# NTC.net
KiCad netlist of a schematic drawn in Altium Designer
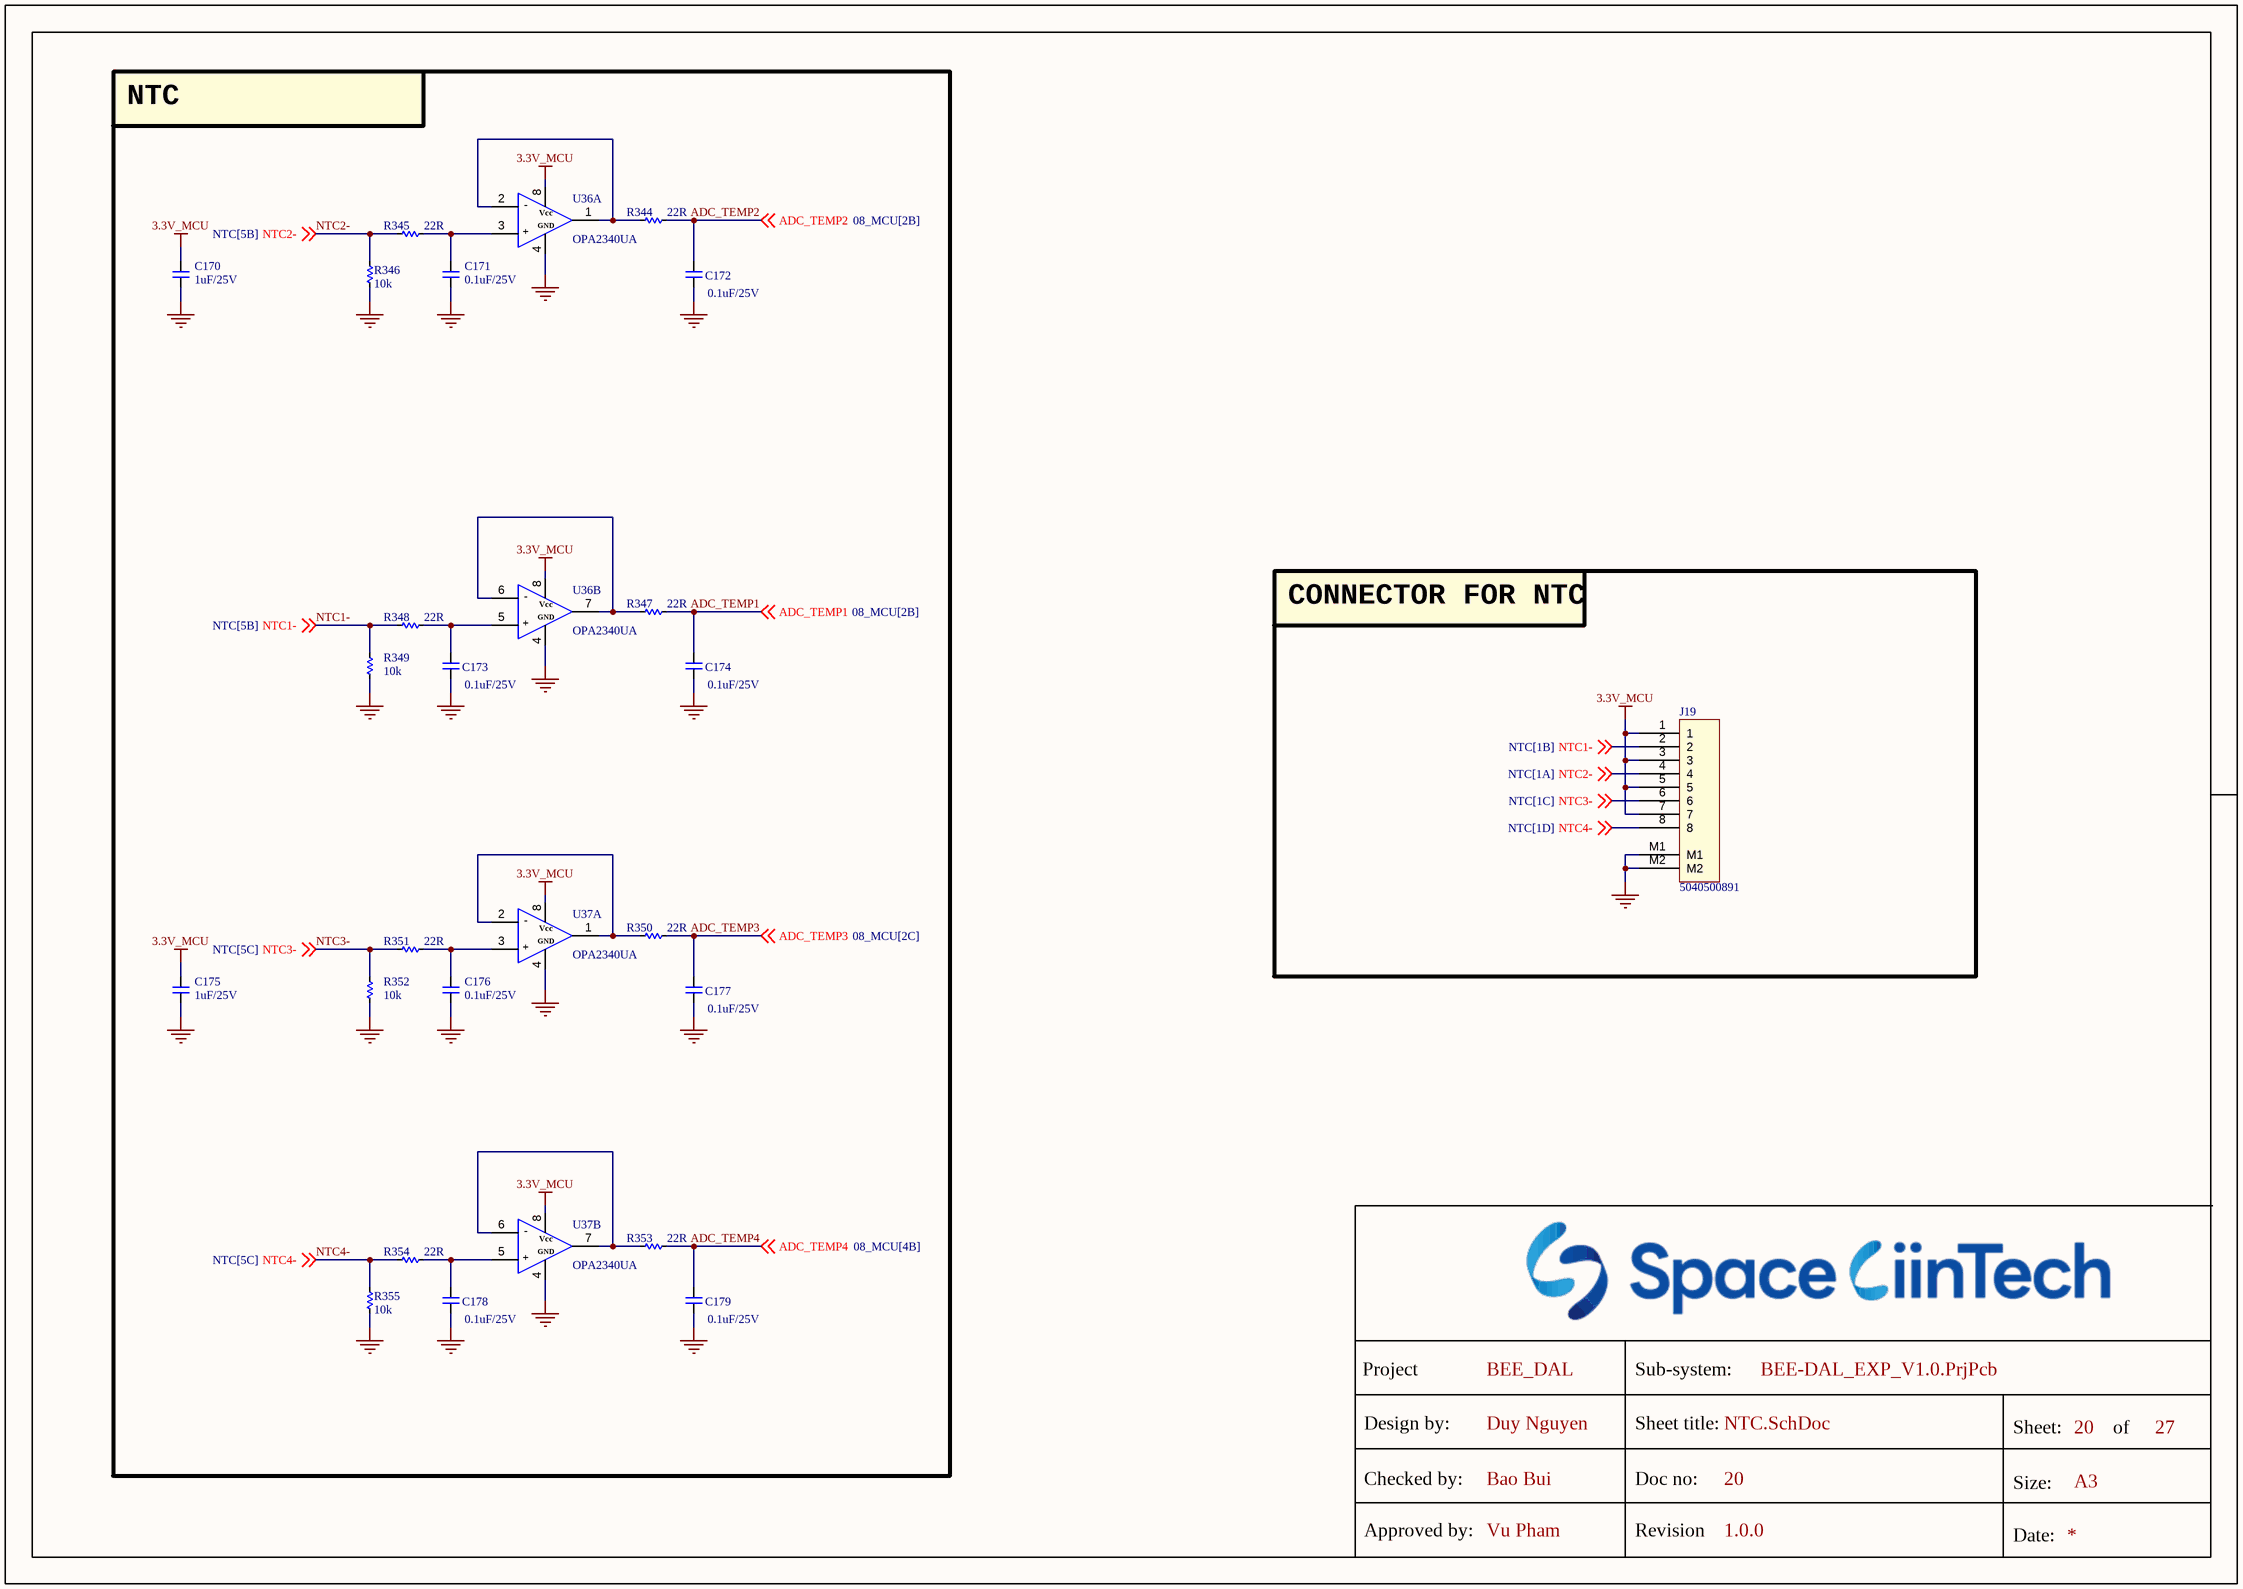
[diagram p0: NTC.SchDoc]

(export (version "E")
  (design (tool "Eeschema 10.0.6"))
  (components
    (comp (ref "C170")
      (value "1uF/25V")
      (footprint "CAP_C_1005X60")
      (description "CAP")
      (libsource (lib "LABLIB") (part "_CAP_C_2"))
    )
    (comp (ref "C171")
      (value "0.1uF/25V")
      (footprint "CAP_C_1005X60")
      (description "CAP")
      (libsource (lib "LABLIB") (part "_CAP_C_2"))
    )
    (comp (ref "C172")
      (value "0.1uF/25V")
      (footprint "CAP_C_1005X60")
      (description "CAP")
      (libsource (lib "LABLIB") (part "_CAP_C_2"))
    )
    (comp (ref "C173")
      (value "0.1uF/25V")
      (footprint "CAP_C_1005X60")
      (description "CAP")
      (libsource (lib "LABLIB") (part "_CAP_C_2"))
    )
    (comp (ref "C174")
      (value "0.1uF/25V")
      (footprint "CAP_C_1005X60")
      (description "CAP")
      (libsource (lib "LABLIB") (part "_CAP_C_2"))
    )
    (comp (ref "C175")
      (value "1uF/25V")
      (footprint "CAP_C_1005X60")
      (description "CAP")
      (libsource (lib "LABLIB") (part "_CAP_C_2"))
    )
    (comp (ref "C176")
      (value "0.1uF/25V")
      (footprint "CAP_C_1005X60")
      (description "CAP")
      (libsource (lib "LABLIB") (part "_CAP_C_2"))
    )
    (comp (ref "C177")
      (value "0.1uF/25V")
      (footprint "CAP_C_1005X60")
      (description "CAP")
      (libsource (lib "LABLIB") (part "_CAP_C_2"))
    )
    (comp (ref "C178")
      (value "0.1uF/25V")
      (footprint "CAP_C_1005X60")
      (description "CAP")
      (libsource (lib "LABLIB") (part "_CAP_C_2"))
    )
    (comp (ref "C179")
      (value "0.1uF/25V")
      (footprint "CAP_C_1005X60")
      (description "CAP")
      (libsource (lib "LABLIB") (part "_CAP_C_2"))
    )
    (comp (ref "J19")
      (value "5040500891")
      (footprint "MOLEX_5040500891")
      (libsource (lib "LABLIB") (part "Header 8x1_2M"))
    )
    (comp (ref "R344")
      (value "22R")
      (footprint "RES_C_1005X40")
      (description "RES")
      (libsource (lib "LABLIB") (part "_RES_B_2"))
    )
    (comp (ref "R345")
      (value "22R")
      (footprint "RES_C_1005X40")
      (description "RES")
      (libsource (lib "LABLIB") (part "_RES_B_2"))
    )
    (comp (ref "R346")
      (value "10k")
      (footprint "RES_C_1005X40")
      (description "RES")
      (libsource (lib "LABLIB") (part "_RES_B_2"))
    )
    (comp (ref "R347")
      (value "22R")
      (footprint "RES_C_1005X40")
      (description "RES")
      (libsource (lib "LABLIB") (part "_RES_B_2"))
    )
    (comp (ref "R348")
      (value "22R")
      (footprint "RES_C_1005X40")
      (description "RES")
      (libsource (lib "LABLIB") (part "_RES_B_2"))
    )
    (comp (ref "R349")
      (value "10k")
      (footprint "RES_C_1005X40")
      (description "RES")
      (libsource (lib "LABLIB") (part "_RES_B_2"))
    )
    (comp (ref "R350")
      (value "22R")
      (footprint "RES_C_1005X40")
      (description "RES")
      (libsource (lib "LABLIB") (part "_RES_B_2"))
    )
    (comp (ref "R351")
      (value "22R")
      (footprint "RES_C_1005X40")
      (description "RES")
      (libsource (lib "LABLIB") (part "_RES_B_2"))
    )
    (comp (ref "R352")
      (value "10k")
      (footprint "RES_C_1005X40")
      (description "RES")
      (libsource (lib "LABLIB") (part "_RES_B_2"))
    )
    (comp (ref "R353")
      (value "22R")
      (footprint "RES_C_1005X40")
      (description "RES")
      (libsource (lib "LABLIB") (part "_RES_B_2"))
    )
    (comp (ref "R354")
      (value "22R")
      (footprint "RES_C_1005X40")
      (description "RES")
      (libsource (lib "LABLIB") (part "_RES_B_2"))
    )
    (comp (ref "R355")
      (value "10k")
      (footprint "RES_C_1005X40")
      (description "RES")
      (libsource (lib "LABLIB") (part "_RES_B_2"))
    )
    (comp (ref "U36")
      (value "OPA2340UA")
      (footprint "SOIC127P602X173-8N")
      (libsource (lib "BEE-DAL_EXP_sche") (part "OPA2340UA"))
    )
    (comp (ref "U37")
      (value "OPA2340UA")
      (footprint "SOIC127P602X173-8N")
      (libsource (lib "BEE-DAL_EXP_sche") (part "OPA2340UA"))
    )
  )
  (nets
    (net (code "1") (name "3.3V_MCU") (class "Default")
      (node (ref "C170") (pin "2") (pinfunction "2_2") (pintype "passive"))
      (node (ref "C175") (pin "2") (pinfunction "2_2") (pintype "passive"))
      (node (ref "J19") (pin "1") (pinfunction "1_1") (pintype "passive"))
      (node (ref "J19") (pin "3") (pinfunction "3_3") (pintype "passive"))
      (node (ref "J19") (pin "5") (pinfunction "5_5") (pintype "passive"))
      (node (ref "J19") (pin "7") (pinfunction "7_7") (pintype "passive"))
      (node (ref "U36") (pin "8") (pinfunction "8_8") (pintype "passive"))
      (node (ref "U37") (pin "8") (pinfunction "8_8") (pintype "passive"))
    )
    (net (code "2") (name "ADC_TEMP1") (class "Default")
      (node (ref "C174") (pin "2") (pinfunction "2_2") (pintype "passive"))
      (node (ref "R347") (pin "2") (pinfunction "2_2") (pintype "passive"))
    )
    (net (code "3") (name "ADC_TEMP2") (class "Default")
      (node (ref "C172") (pin "2") (pinfunction "2_2") (pintype "passive"))
      (node (ref "R344") (pin "2") (pinfunction "2_2") (pintype "passive"))
    )
    (net (code "4") (name "ADC_TEMP3") (class "Default")
      (node (ref "C177") (pin "2") (pinfunction "2_2") (pintype "passive"))
      (node (ref "R350") (pin "2") (pinfunction "2_2") (pintype "passive"))
    )
    (net (code "5") (name "ADC_TEMP4") (class "Default")
      (node (ref "C179") (pin "2") (pinfunction "2_2") (pintype "passive"))
      (node (ref "R353") (pin "2") (pinfunction "2_2") (pintype "passive"))
    )
    (net (code "6") (name "GND") (class "Default")
      (node (ref "C170") (pin "1") (pinfunction "1_1") (pintype "passive"))
      (node (ref "C171") (pin "1") (pinfunction "1_1") (pintype "passive"))
      (node (ref "C172") (pin "1") (pinfunction "1_1") (pintype "passive"))
      (node (ref "C173") (pin "1") (pinfunction "1_1") (pintype "passive"))
      (node (ref "C174") (pin "1") (pinfunction "1_1") (pintype "passive"))
      (node (ref "C175") (pin "1") (pinfunction "1_1") (pintype "passive"))
      (node (ref "C176") (pin "1") (pinfunction "1_1") (pintype "passive"))
      (node (ref "C177") (pin "1") (pinfunction "1_1") (pintype "passive"))
      (node (ref "C178") (pin "1") (pinfunction "1_1") (pintype "passive"))
      (node (ref "C179") (pin "1") (pinfunction "1_1") (pintype "passive"))
      (node (ref "J19") (pin "M1") (pinfunction "M1_M1") (pintype "passive"))
      (node (ref "J19") (pin "M2") (pinfunction "M2_M2") (pintype "passive"))
      (node (ref "R346") (pin "1") (pinfunction "1_1") (pintype "passive"))
      (node (ref "R349") (pin "1") (pinfunction "1_1") (pintype "passive"))
      (node (ref "R352") (pin "1") (pinfunction "1_1") (pintype "passive"))
      (node (ref "R355") (pin "1") (pinfunction "1_1") (pintype "passive"))
      (node (ref "U36") (pin "4") (pinfunction "4_4") (pintype "passive"))
      (node (ref "U37") (pin "4") (pinfunction "4_4") (pintype "passive"))
    )
    (net (code "7") (name "NTC1-") (class "Default")
      (node (ref "J19") (pin "2") (pinfunction "2_2") (pintype "passive"))
      (node (ref "R348") (pin "1") (pinfunction "1_1") (pintype "passive"))
      (node (ref "R349") (pin "2") (pinfunction "2_2") (pintype "passive"))
    )
    (net (code "8") (name "NTC2-") (class "Default")
      (node (ref "J19") (pin "4") (pinfunction "4_4") (pintype "passive"))
      (node (ref "R345") (pin "1") (pinfunction "1_1") (pintype "passive"))
      (node (ref "R346") (pin "2") (pinfunction "2_2") (pintype "passive"))
    )
    (net (code "9") (name "NTC3-") (class "Default")
      (node (ref "J19") (pin "6") (pinfunction "6_6") (pintype "passive"))
      (node (ref "R351") (pin "1") (pinfunction "1_1") (pintype "passive"))
      (node (ref "R352") (pin "2") (pinfunction "2_2") (pintype "passive"))
    )
    (net (code "10") (name "NTC4-") (class "Default")
      (node (ref "J19") (pin "8") (pinfunction "8_8") (pintype "passive"))
      (node (ref "R354") (pin "1") (pinfunction "1_1") (pintype "passive"))
      (node (ref "R355") (pin "2") (pinfunction "2_2") (pintype "passive"))
    )
    (net (code "11") (name "Net-(C171-Pad2)") (class "Default")
      (node (ref "C171") (pin "2") (pinfunction "2_2") (pintype "passive"))
      (node (ref "R345") (pin "2") (pinfunction "2_2") (pintype "passive"))
      (node (ref "U36") (pin "3") (pinfunction "3_3") (pintype "passive"))
    )
    (net (code "12") (name "Net-(C173-Pad2)") (class "Default")
      (node (ref "C173") (pin "2") (pinfunction "2_2") (pintype "passive"))
      (node (ref "R348") (pin "2") (pinfunction "2_2") (pintype "passive"))
      (node (ref "U36") (pin "5") (pinfunction "5_5") (pintype "passive"))
    )
    (net (code "13") (name "Net-(C176-Pad2)") (class "Default")
      (node (ref "C176") (pin "2") (pinfunction "2_2") (pintype "passive"))
      (node (ref "R351") (pin "2") (pinfunction "2_2") (pintype "passive"))
      (node (ref "U37") (pin "3") (pinfunction "3_3") (pintype "passive"))
    )
    (net (code "14") (name "Net-(C178-Pad2)") (class "Default")
      (node (ref "C178") (pin "2") (pinfunction "2_2") (pintype "passive"))
      (node (ref "R354") (pin "2") (pinfunction "2_2") (pintype "passive"))
      (node (ref "U37") (pin "5") (pinfunction "5_5") (pintype "passive"))
    )
    (net (code "15") (name "Net-(R344-Pad1)") (class "Default")
      (node (ref "R344") (pin "1") (pinfunction "1_1") (pintype "passive"))
      (node (ref "U36") (pin "1") (pinfunction "1_1") (pintype "passive"))
      (node (ref "U36") (pin "2") (pinfunction "2_2") (pintype "passive"))
    )
    (net (code "16") (name "Net-(R347-Pad1)") (class "Default")
      (node (ref "R347") (pin "1") (pinfunction "1_1") (pintype "passive"))
      (node (ref "U36") (pin "6") (pinfunction "6_6") (pintype "passive"))
      (node (ref "U36") (pin "7") (pinfunction "7_7") (pintype "passive"))
    )
    (net (code "17") (name "Net-(R350-Pad1)") (class "Default")
      (node (ref "R350") (pin "1") (pinfunction "1_1") (pintype "passive"))
      (node (ref "U37") (pin "1") (pinfunction "1_1") (pintype "passive"))
      (node (ref "U37") (pin "2") (pinfunction "2_2") (pintype "passive"))
    )
    (net (code "18") (name "Net-(R353-Pad1)") (class "Default")
      (node (ref "R353") (pin "1") (pinfunction "1_1") (pintype "passive"))
      (node (ref "U37") (pin "6") (pinfunction "6_6") (pintype "passive"))
      (node (ref "U37") (pin "7") (pinfunction "7_7") (pintype "passive"))
    )
  )
)
